# Sch_v4.net
KiCad netlist of a schematic drawn in EAGLE
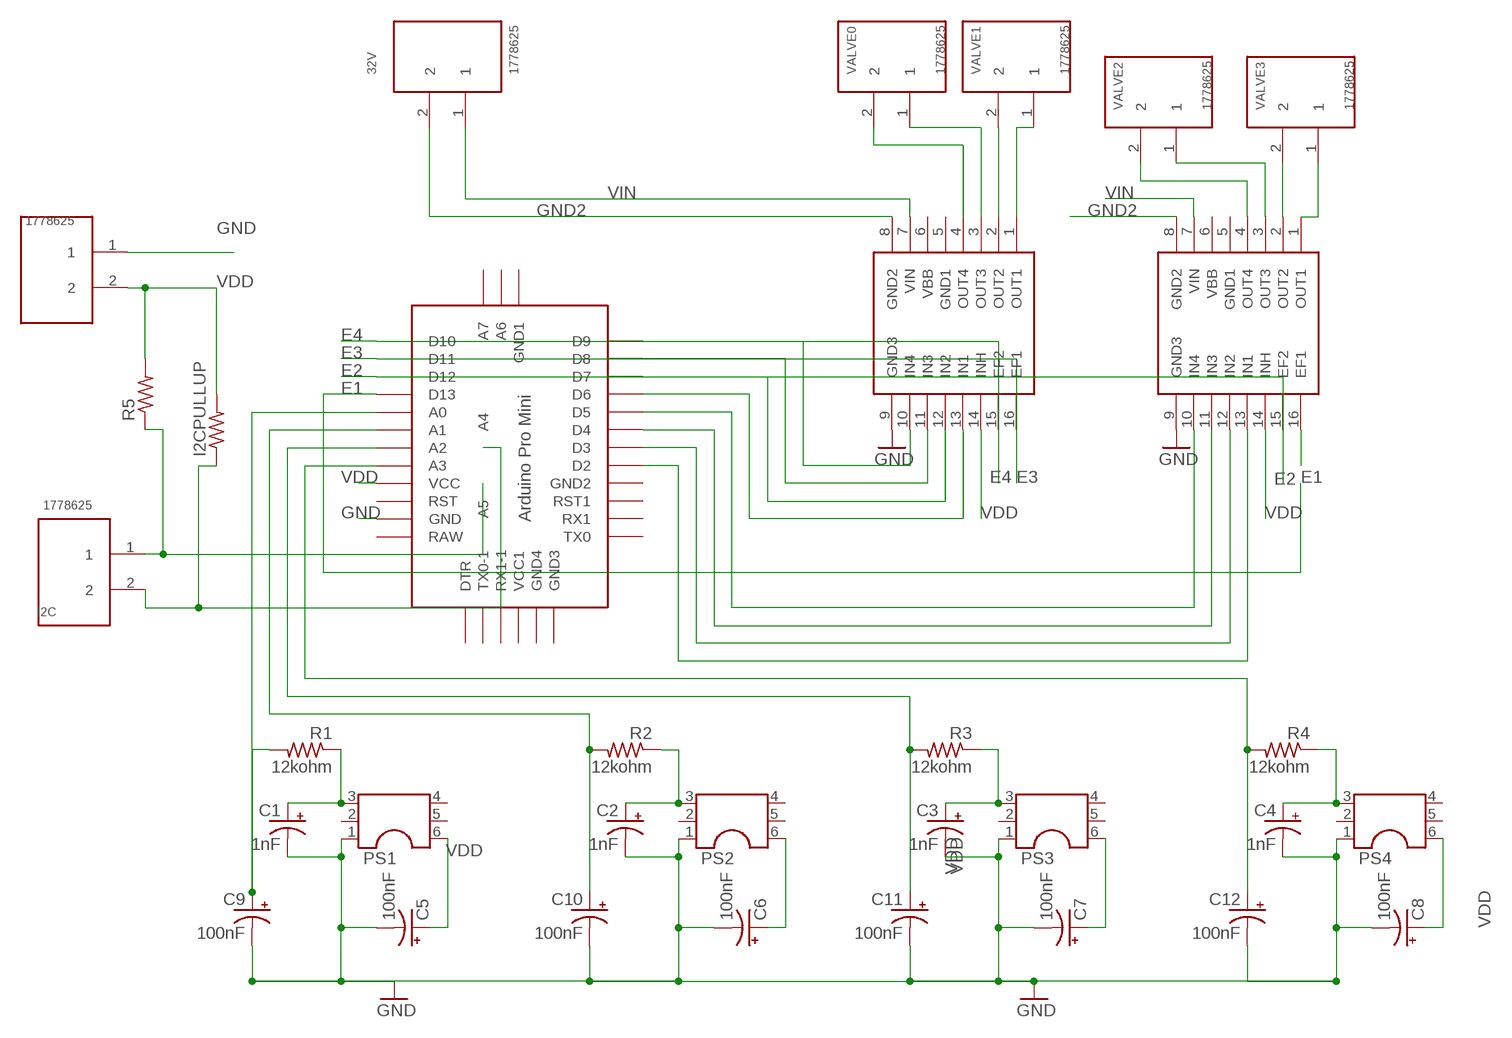
[diagram p0: schematic, sheet 1]

(export (version "E")
  (design (tool "Eeschema 10.0.6"))
  (components
    (comp (ref "5V")
      (value "1778625")
      (footprint "eagle-import:1778625")
      (fields (field (name "MF") "Phoenix Contact"))
      (libsource (lib "eagle-import") (part "1778625"))
    )
    (comp (ref "32V")
      (value "1778625")
      (footprint "eagle-import:1778625")
      (fields (field (name "MF") "Phoenix Contact"))
      (libsource (lib "eagle-import") (part "1778625"))
    )
    (comp (ref "C1")
      (value "1nF")
      (footprint "eagle-import:E2,5-5")
      (libsource (lib "eagle-import") (part "CPOL-USE2.5-5"))
    )
    (comp (ref "C2")
      (value "1nF")
      (footprint "eagle-import:E2,5-5")
      (libsource (lib "eagle-import") (part "CPOL-USE2.5-5"))
    )
    (comp (ref "C3")
      (value "1nF")
      (footprint "eagle-import:E2,5-5")
      (libsource (lib "eagle-import") (part "CPOL-USE2.5-5"))
    )
    (comp (ref "C4")
      (value "1nF")
      (footprint "eagle-import:E2,5-5")
      (libsource (lib "eagle-import") (part "CPOL-USE2.5-5"))
    )
    (comp (ref "C5")
      (value "100nF")
      (footprint "eagle-import:E2,5-5")
      (libsource (lib "eagle-import") (part "CPOL-USE2.5-5"))
    )
    (comp (ref "C6")
      (value "100nF")
      (footprint "eagle-import:E2,5-5")
      (libsource (lib "eagle-import") (part "CPOL-USE2.5-5"))
    )
    (comp (ref "C7")
      (value "100nF")
      (footprint "eagle-import:E2,5-5")
      (libsource (lib "eagle-import") (part "CPOL-USE2.5-5"))
    )
    (comp (ref "C8")
      (value "100nF")
      (footprint "eagle-import:E2,5-5")
      (libsource (lib "eagle-import") (part "CPOL-USE2.5-5"))
    )
    (comp (ref "C9")
      (value "100nF")
      (footprint "eagle-import:E2,5-5")
      (libsource (lib "eagle-import") (part "CPOL-USE2.5-5"))
    )
    (comp (ref "C10")
      (value "100nF")
      (footprint "eagle-import:E2,5-5")
      (libsource (lib "eagle-import") (part "CPOL-USE2.5-5"))
    )
    (comp (ref "C11")
      (value "100nF")
      (footprint "eagle-import:E2,5-5")
      (libsource (lib "eagle-import") (part "CPOL-USE2.5-5"))
    )
    (comp (ref "C12")
      (value "100nF")
      (footprint "eagle-import:E2,5-5")
      (libsource (lib "eagle-import") (part "CPOL-USE2.5-5"))
    )
    (comp (ref "I2C")
      (value "1778625")
      (footprint "eagle-import:1778625")
      (fields (field (name "MF") "Phoenix Contact"))
      (libsource (lib "eagle-import") (part "1778625"))
    )
    (comp (ref "I2CPULLUP")
      (value "R-US_0204/7")
      (footprint "eagle-import:0204_7")
      (libsource (lib "eagle-import") (part "R-US_0204/7"))
    )
    (comp (ref "PS1")
      (value "ABPDRNN100PGAA5")
      (footprint "eagle-import:ABPDRNN100PGAA5")
      (libsource (lib "eagle-import") (part "ABPDRNN100PGAA5"))
    )
    (comp (ref "PS2")
      (value "ABPDRNN100PGAA5")
      (footprint "eagle-import:ABPDRNN100PGAA5")
      (libsource (lib "eagle-import") (part "ABPDRNN100PGAA5"))
    )
    (comp (ref "PS3")
      (value "ABPDRNN100PGAA5")
      (footprint "eagle-import:ABPDRNN100PGAA5")
      (libsource (lib "eagle-import") (part "ABPDRNN100PGAA5"))
    )
    (comp (ref "PS4")
      (value "ABPDRNN100PGAA5")
      (footprint "eagle-import:ABPDRNN100PGAA5")
      (libsource (lib "eagle-import") (part "ABPDRNN100PGAA5"))
    )
    (comp (ref "R1")
      (value "12kohm")
      (footprint "eagle-import:0204_7")
      (libsource (lib "eagle-import") (part "R-US_0204/7"))
    )
    (comp (ref "R2")
      (value "12kohm")
      (footprint "eagle-import:0204_7")
      (libsource (lib "eagle-import") (part "R-US_0204/7"))
    )
    (comp (ref "R3")
      (value "12kohm")
      (footprint "eagle-import:0204_7")
      (libsource (lib "eagle-import") (part "R-US_0204/7"))
    )
    (comp (ref "R4")
      (value "12kohm")
      (footprint "eagle-import:0204_7")
      (libsource (lib "eagle-import") (part "R-US_0204/7"))
    )
    (comp (ref "R5")
      (value "R-US_0204/7")
      (footprint "eagle-import:0204_7")
      (libsource (lib "eagle-import") (part "R-US_0204/7"))
    )
    (comp (ref "U$1")
      (value "ABK-PRO-MINI")
      (footprint "eagle-import:ABK-PRO-MINI")
      (libsource (lib "eagle-import") (part "ABK-PRO-MINI"))
    )
    (comp (ref "U$2")
      (value "A4990")
      (footprint "eagle-import:A4990")
      (libsource (lib "eagle-import") (part "A4990"))
    )
    (comp (ref "U$3")
      (value "A4990")
      (footprint "eagle-import:A4990")
      (libsource (lib "eagle-import") (part "A4990"))
    )
    (comp (ref "VALVE0")
      (value "1778625")
      (footprint "eagle-import:1778625")
      (fields (field (name "MF") "Phoenix Contact"))
      (libsource (lib "eagle-import") (part "1778625"))
    )
    (comp (ref "VALVE1")
      (value "1778625")
      (footprint "eagle-import:1778625")
      (fields (field (name "MF") "Phoenix Contact"))
      (libsource (lib "eagle-import") (part "1778625"))
    )
    (comp (ref "VALVE2")
      (value "1778625")
      (footprint "eagle-import:1778625")
      (fields (field (name "MF") "Phoenix Contact"))
      (libsource (lib "eagle-import") (part "1778625"))
    )
    (comp (ref "VALVE3")
      (value "1778625")
      (footprint "eagle-import:1778625")
      (fields (field (name "MF") "Phoenix Contact"))
      (libsource (lib "eagle-import") (part "1778625"))
    )
  )
  (nets
    (net (code "1") (name "/E1") (class "Default")
      (node (ref "U$1") (pin "D13") (pinfunction "D13_D13") (pintype "bidirectional"))
      (node (ref "U$3") (pin "16") (pinfunction "EF1_16") (pintype "bidirectional"))
    )
    (net (code "2") (name "/E2") (class "Default")
      (node (ref "U$1") (pin "D12") (pinfunction "D12_D12") (pintype "bidirectional"))
      (node (ref "U$3") (pin "15") (pinfunction "EF2_15") (pintype "bidirectional"))
    )
    (net (code "3") (name "/E3") (class "Default")
      (node (ref "U$1") (pin "D11") (pinfunction "D11_D11") (pintype "bidirectional"))
      (node (ref "U$2") (pin "16") (pinfunction "EF1_16") (pintype "bidirectional"))
    )
    (net (code "4") (name "/E4") (class "Default")
      (node (ref "U$1") (pin "D10") (pinfunction "D10_D10") (pintype "bidirectional"))
      (node (ref "U$2") (pin "15") (pinfunction "EF2_15") (pintype "bidirectional"))
    )
    (net (code "5") (name "/GND2") (class "Default")
      (node (ref "32V") (pin "2") (pinfunction "2_2") (pintype "bidirectional"))
      (node (ref "U$2") (pin "8") (pinfunction "GND2_8") (pintype "bidirectional"))
      (node (ref "U$3") (pin "8") (pinfunction "GND2_8") (pintype "bidirectional"))
    )
    (net (code "6") (name "/VDD") (class "Default")
      (node (ref "5V") (pin "2") (pinfunction "2_2") (pintype "bidirectional"))
      (node (ref "C5") (pin "+") (pinfunction "+_+") (pintype "passive"))
      (node (ref "C6") (pin "+") (pinfunction "+_+") (pintype "passive"))
      (node (ref "C7") (pin "+") (pinfunction "+_+") (pintype "passive"))
      (node (ref "C8") (pin "+") (pinfunction "+_+") (pintype "passive"))
      (node (ref "I2C") (pin "2") (pinfunction "2_2") (pintype "bidirectional"))
      (node (ref "I2CPULLUP") (pin "1") (pinfunction "1_1") (pintype "passive"))
      (node (ref "I2CPULLUP") (pin "2") (pinfunction "2_2") (pintype "passive"))
      (node (ref "PS1") (pin "6") (pinfunction "6_6") (pintype "passive"))
      (node (ref "PS2") (pin "6") (pinfunction "6_6") (pintype "passive"))
      (node (ref "PS3") (pin "6") (pinfunction "6_6") (pintype "passive"))
      (node (ref "PS4") (pin "6") (pinfunction "6_6") (pintype "passive"))
      (node (ref "R5") (pin "2") (pinfunction "2_2") (pintype "passive"))
      (node (ref "U$1") (pin "A4") (pinfunction "A4_A4") (pintype "bidirectional"))
      (node (ref "U$1") (pin "VCC") (pinfunction "VCC_VCC") (pintype "bidirectional"))
      (node (ref "U$2") (pin "14") (pinfunction "INH_14") (pintype "bidirectional"))
      (node (ref "U$3") (pin "14") (pinfunction "INH_14") (pintype "bidirectional"))
    )
    (net (code "7") (name "/VIN") (class "Default")
      (node (ref "32V") (pin "1") (pinfunction "1_1") (pintype "bidirectional"))
      (node (ref "U$2") (pin "7") (pinfunction "VIN_7") (pintype "bidirectional"))
      (node (ref "U$3") (pin "7") (pinfunction "VIN_7") (pintype "bidirectional"))
    )
    (net (code "8") (name "GND") (class "Default")
      (node (ref "5V") (pin "1") (pinfunction "1_1") (pintype "bidirectional"))
      (node (ref "C1") (pin "-") (pinfunction "-_-") (pintype "passive"))
      (node (ref "C10") (pin "-") (pinfunction "-_-") (pintype "passive"))
      (node (ref "C11") (pin "-") (pinfunction "-_-") (pintype "passive"))
      (node (ref "C12") (pin "-") (pinfunction "-_-") (pintype "passive"))
      (node (ref "C2") (pin "-") (pinfunction "-_-") (pintype "passive"))
      (node (ref "C3") (pin "-") (pinfunction "-_-") (pintype "passive"))
      (node (ref "C4") (pin "-") (pinfunction "-_-") (pintype "passive"))
      (node (ref "C5") (pin "-") (pinfunction "-_-") (pintype "passive"))
      (node (ref "C6") (pin "-") (pinfunction "-_-") (pintype "passive"))
      (node (ref "C7") (pin "-") (pinfunction "-_-") (pintype "passive"))
      (node (ref "C8") (pin "-") (pinfunction "-_-") (pintype "passive"))
      (node (ref "C9") (pin "-") (pinfunction "-_-") (pintype "passive"))
      (node (ref "PS1") (pin "1") (pinfunction "1_1") (pintype "passive"))
      (node (ref "PS2") (pin "1") (pinfunction "1_1") (pintype "passive"))
      (node (ref "PS3") (pin "1") (pinfunction "1_1") (pintype "passive"))
      (node (ref "PS4") (pin "1") (pinfunction "1_1") (pintype "passive"))
      (node (ref "U$1") (pin "GND") (pinfunction "GND_GND") (pintype "bidirectional"))
      (node (ref "U$2") (pin "9") (pinfunction "GND3_9") (pintype "bidirectional"))
      (node (ref "U$3") (pin "9") (pinfunction "GND3_9") (pintype "bidirectional"))
    )
    (net (code "9") (name "Net-(C1-Pad+)") (class "Default")
      (node (ref "C1") (pin "+") (pinfunction "+_+") (pintype "passive"))
      (node (ref "PS1") (pin "3") (pinfunction "3_3") (pintype "passive"))
      (node (ref "R1") (pin "1") (pinfunction "1_1") (pintype "passive"))
    )
    (net (code "10") (name "Net-(C2-Pad+)") (class "Default")
      (node (ref "C2") (pin "+") (pinfunction "+_+") (pintype "passive"))
      (node (ref "PS2") (pin "3") (pinfunction "3_3") (pintype "passive"))
      (node (ref "R2") (pin "1") (pinfunction "1_1") (pintype "passive"))
    )
    (net (code "11") (name "Net-(C3-Pad+)") (class "Default")
      (node (ref "C3") (pin "+") (pinfunction "+_+") (pintype "passive"))
      (node (ref "PS3") (pin "3") (pinfunction "3_3") (pintype "passive"))
      (node (ref "R3") (pin "1") (pinfunction "1_1") (pintype "passive"))
    )
    (net (code "12") (name "Net-(C4-Pad+)") (class "Default")
      (node (ref "C4") (pin "+") (pinfunction "+_+") (pintype "passive"))
      (node (ref "PS4") (pin "3") (pinfunction "3_3") (pintype "passive"))
      (node (ref "R4") (pin "1") (pinfunction "1_1") (pintype "passive"))
    )
    (net (code "13") (name "Net-(C9-Pad+)") (class "Default")
      (node (ref "C9") (pin "+") (pinfunction "+_+") (pintype "passive"))
      (node (ref "R1") (pin "2") (pinfunction "2_2") (pintype "passive"))
      (node (ref "U$1") (pin "A0") (pinfunction "A0_A0") (pintype "bidirectional"))
    )
    (net (code "14") (name "Net-(C10-Pad+)") (class "Default")
      (node (ref "C10") (pin "+") (pinfunction "+_+") (pintype "passive"))
      (node (ref "R2") (pin "2") (pinfunction "2_2") (pintype "passive"))
      (node (ref "U$1") (pin "A1") (pinfunction "A1_A1") (pintype "bidirectional"))
    )
    (net (code "15") (name "Net-(C11-Pad+)") (class "Default")
      (node (ref "C11") (pin "+") (pinfunction "+_+") (pintype "passive"))
      (node (ref "R3") (pin "2") (pinfunction "2_2") (pintype "passive"))
      (node (ref "U$1") (pin "A2") (pinfunction "A2_A2") (pintype "bidirectional"))
    )
    (net (code "16") (name "Net-(C12-Pad+)") (class "Default")
      (node (ref "C12") (pin "+") (pinfunction "+_+") (pintype "passive"))
      (node (ref "R4") (pin "2") (pinfunction "2_2") (pintype "passive"))
      (node (ref "U$1") (pin "A3") (pinfunction "A3_A3") (pintype "bidirectional"))
    )
    (net (code "17") (name "Net-(I2C-Pad1)") (class "Default")
      (node (ref "I2C") (pin "1") (pinfunction "1_1") (pintype "bidirectional"))
      (node (ref "R5") (pin "1") (pinfunction "1_1") (pintype "passive"))
      (node (ref "U$1") (pin "A5") (pinfunction "A5_A5") (pintype "bidirectional"))
    )
    (net (code "18") (name "Net-(U$2-IN1)") (class "Default")
      (node (ref "U$1") (pin "D6") (pinfunction "D6_D6") (pintype "bidirectional"))
      (node (ref "U$2") (pin "13") (pinfunction "IN1_13") (pintype "bidirectional"))
    )
    (net (code "19") (name "Net-(U$2-IN2)") (class "Default")
      (node (ref "U$1") (pin "D7") (pinfunction "D7_D7") (pintype "bidirectional"))
      (node (ref "U$2") (pin "12") (pinfunction "IN2_12") (pintype "bidirectional"))
    )
    (net (code "20") (name "Net-(U$2-IN3)") (class "Default")
      (node (ref "U$1") (pin "D8") (pinfunction "D8_D8") (pintype "bidirectional"))
      (node (ref "U$2") (pin "11") (pinfunction "IN3_11") (pintype "bidirectional"))
    )
    (net (code "21") (name "Net-(U$2-IN4)") (class "Default")
      (node (ref "U$1") (pin "D9") (pinfunction "D9_D9") (pintype "bidirectional"))
      (node (ref "U$2") (pin "10") (pinfunction "IN4_10") (pintype "bidirectional"))
    )
    (net (code "22") (name "Net-(U$2-OUT1)") (class "Default")
      (node (ref "U$2") (pin "1") (pinfunction "OUT1_1") (pintype "bidirectional"))
      (node (ref "VALVE1") (pin "1") (pinfunction "1_1") (pintype "bidirectional"))
    )
    (net (code "23") (name "Net-(U$2-OUT2)") (class "Default")
      (node (ref "U$2") (pin "2") (pinfunction "OUT2_2") (pintype "bidirectional"))
      (node (ref "VALVE1") (pin "2") (pinfunction "2_2") (pintype "bidirectional"))
    )
    (net (code "24") (name "Net-(U$2-OUT3)") (class "Default")
      (node (ref "U$2") (pin "3") (pinfunction "OUT3_3") (pintype "bidirectional"))
      (node (ref "VALVE0") (pin "1") (pinfunction "1_1") (pintype "bidirectional"))
    )
    (net (code "25") (name "Net-(U$2-OUT4)") (class "Default")
      (node (ref "U$2") (pin "4") (pinfunction "OUT4_4") (pintype "bidirectional"))
      (node (ref "VALVE0") (pin "2") (pinfunction "2_2") (pintype "bidirectional"))
    )
    (net (code "26") (name "Net-(U$3-IN1)") (class "Default")
      (node (ref "U$1") (pin "D2") (pinfunction "D2_D2") (pintype "bidirectional"))
      (node (ref "U$3") (pin "13") (pinfunction "IN1_13") (pintype "bidirectional"))
    )
    (net (code "27") (name "Net-(U$3-IN2)") (class "Default")
      (node (ref "U$1") (pin "D3") (pinfunction "D3_D3") (pintype "bidirectional"))
      (node (ref "U$3") (pin "12") (pinfunction "IN2_12") (pintype "bidirectional"))
    )
    (net (code "28") (name "Net-(U$3-IN3)") (class "Default")
      (node (ref "U$1") (pin "D4") (pinfunction "D4_D4") (pintype "bidirectional"))
      (node (ref "U$3") (pin "11") (pinfunction "IN3_11") (pintype "bidirectional"))
    )
    (net (code "29") (name "Net-(U$3-IN4)") (class "Default")
      (node (ref "U$1") (pin "D5") (pinfunction "D5_D5") (pintype "bidirectional"))
      (node (ref "U$3") (pin "10") (pinfunction "IN4_10") (pintype "bidirectional"))
    )
    (net (code "30") (name "Net-(U$3-OUT1)") (class "Default")
      (node (ref "U$3") (pin "1") (pinfunction "OUT1_1") (pintype "bidirectional"))
      (node (ref "VALVE3") (pin "1") (pinfunction "1_1") (pintype "bidirectional"))
    )
    (net (code "31") (name "Net-(U$3-OUT2)") (class "Default")
      (node (ref "U$3") (pin "2") (pinfunction "OUT2_2") (pintype "bidirectional"))
      (node (ref "VALVE3") (pin "2") (pinfunction "2_2") (pintype "bidirectional"))
    )
    (net (code "32") (name "Net-(U$3-OUT3)") (class "Default")
      (node (ref "U$3") (pin "3") (pinfunction "OUT3_3") (pintype "bidirectional"))
      (node (ref "VALVE2") (pin "1") (pinfunction "1_1") (pintype "bidirectional"))
    )
    (net (code "33") (name "Net-(U$3-OUT4)") (class "Default")
      (node (ref "U$3") (pin "4") (pinfunction "OUT4_4") (pintype "bidirectional"))
      (node (ref "VALVE2") (pin "2") (pinfunction "2_2") (pintype "bidirectional"))
    )
    (net (code "34") (name "unconnected-(PS1-Pad2)") (class "Default")
      (node (ref "PS1") (pin "2") (pinfunction "2_2") (pintype "passive"))
    )
    (net (code "35") (name "unconnected-(PS1-Pad4)") (class "Default")
      (node (ref "PS1") (pin "4") (pinfunction "4_4") (pintype "passive"))
    )
    (net (code "36") (name "unconnected-(PS1-Pad5)") (class "Default")
      (node (ref "PS1") (pin "5") (pinfunction "5_5") (pintype "passive"))
    )
    (net (code "37") (name "unconnected-(PS2-Pad2)") (class "Default")
      (node (ref "PS2") (pin "2") (pinfunction "2_2") (pintype "passive"))
    )
    (net (code "38") (name "unconnected-(PS2-Pad4)") (class "Default")
      (node (ref "PS2") (pin "4") (pinfunction "4_4") (pintype "passive"))
    )
    (net (code "39") (name "unconnected-(PS2-Pad5)") (class "Default")
      (node (ref "PS2") (pin "5") (pinfunction "5_5") (pintype "passive"))
    )
    (net (code "40") (name "unconnected-(PS3-Pad2)") (class "Default")
      (node (ref "PS3") (pin "2") (pinfunction "2_2") (pintype "passive"))
    )
    (net (code "41") (name "unconnected-(PS3-Pad4)") (class "Default")
      (node (ref "PS3") (pin "4") (pinfunction "4_4") (pintype "passive"))
    )
    (net (code "42") (name "unconnected-(PS3-Pad5)") (class "Default")
      (node (ref "PS3") (pin "5") (pinfunction "5_5") (pintype "passive"))
    )
    (net (code "43") (name "unconnected-(PS4-Pad2)") (class "Default")
      (node (ref "PS4") (pin "2") (pinfunction "2_2") (pintype "passive"))
    )
    (net (code "44") (name "unconnected-(PS4-Pad4)") (class "Default")
      (node (ref "PS4") (pin "4") (pinfunction "4_4") (pintype "passive"))
    )
    (net (code "45") (name "unconnected-(PS4-Pad5)") (class "Default")
      (node (ref "PS4") (pin "5") (pinfunction "5_5") (pintype "passive"))
    )
    (net (code "46") (name "unconnected-(U$1-GND1-PadGND4)") (class "Default")
      (node (ref "U$1") (pin "GND4") (pinfunction "GND1_GND4") (pintype "bidirectional"))
    )
    (net (code "47") (name "unconnected-(U$1-GND2-PadGND1)") (class "Default")
      (node (ref "U$1") (pin "GND1") (pinfunction "GND2_GND1") (pintype "bidirectional"))
    )
    (net (code "48") (name "unconnected-(U$1-GND3-PadGND2)") (class "Default")
      (node (ref "U$1") (pin "GND2") (pinfunction "GND3_GND2") (pintype "bidirectional"))
    )
    (net (code "49") (name "unconnected-(U$1-GND4-PadGND3)") (class "Default")
      (node (ref "U$1") (pin "GND3") (pinfunction "GND4_GND3") (pintype "bidirectional"))
    )
    (net (code "50") (name "unconnected-(U$1-PadA6)") (class "Default")
      (node (ref "U$1") (pin "A6") (pinfunction "A6_A6") (pintype "bidirectional"))
    )
    (net (code "51") (name "unconnected-(U$1-PadA7)") (class "Default")
      (node (ref "U$1") (pin "A7") (pinfunction "A7_A7") (pintype "bidirectional"))
    )
    (net (code "52") (name "unconnected-(U$1-PadDTR)") (class "Default")
      (node (ref "U$1") (pin "DTR") (pinfunction "DTR_DTR") (pintype "bidirectional"))
    )
    (net (code "53") (name "unconnected-(U$1-PadRAW)") (class "Default")
      (node (ref "U$1") (pin "RAW") (pinfunction "RAW_RAW") (pintype "bidirectional"))
    )
    (net (code "54") (name "unconnected-(U$1-PadRST)") (class "Default")
      (node (ref "U$1") (pin "RST") (pinfunction "RST_RST") (pintype "bidirectional"))
    )
    (net (code "55") (name "unconnected-(U$1-PadRST1)") (class "Default")
      (node (ref "U$1") (pin "RST1") (pinfunction "RST1_RST1") (pintype "bidirectional"))
    )
    (net (code "56") (name "unconnected-(U$1-PadRX1)") (class "Default")
      (node (ref "U$1") (pin "RX1") (pinfunction "RX1_RX1") (pintype "bidirectional"))
    )
    (net (code "57") (name "unconnected-(U$1-PadRX1-1)") (class "Default")
      (node (ref "U$1") (pin "RX1-1") (pinfunction "RX1-1_RX1-1") (pintype "bidirectional"))
    )
    (net (code "58") (name "unconnected-(U$1-PadTX0)") (class "Default")
      (node (ref "U$1") (pin "TX0") (pinfunction "TX0_TX0") (pintype "bidirectional"))
    )
    (net (code "59") (name "unconnected-(U$1-PadTX0-1)") (class "Default")
      (node (ref "U$1") (pin "TX0-1") (pinfunction "TX0-1_TX0-1") (pintype "bidirectional"))
    )
    (net (code "60") (name "unconnected-(U$1-PadVCC1)") (class "Default")
      (node (ref "U$1") (pin "VCC1") (pinfunction "VCC1_VCC1") (pintype "bidirectional"))
    )
    (net (code "61") (name "unconnected-(U$2-GND1-Pad5)") (class "Default")
      (node (ref "U$2") (pin "5") (pinfunction "GND1_5") (pintype "bidirectional"))
    )
    (net (code "62") (name "unconnected-(U$2-VBB-Pad6)") (class "Default")
      (node (ref "U$2") (pin "6") (pinfunction "VBB_6") (pintype "bidirectional"))
    )
    (net (code "63") (name "unconnected-(U$3-GND1-Pad5)") (class "Default")
      (node (ref "U$3") (pin "5") (pinfunction "GND1_5") (pintype "bidirectional"))
    )
    (net (code "64") (name "unconnected-(U$3-VBB-Pad6)") (class "Default")
      (node (ref "U$3") (pin "6") (pinfunction "VBB_6") (pintype "bidirectional"))
    )
  )
)
